# Accessories.net
KiCad netlist of a schematic drawn in Altium Designer
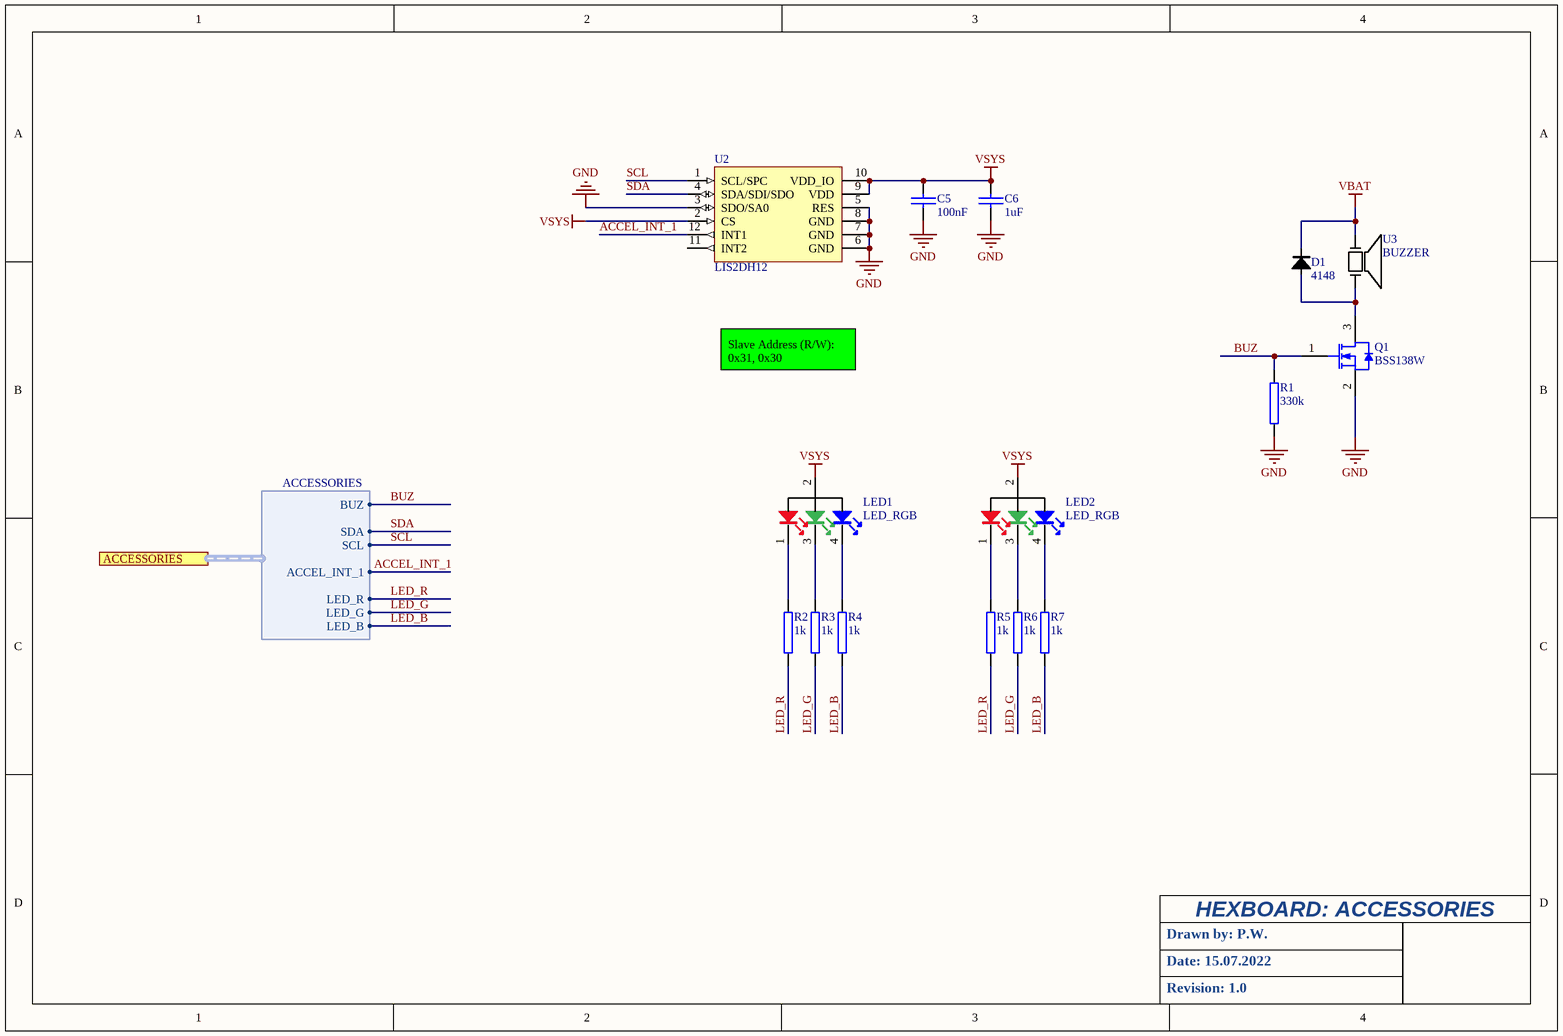
[diagram p0: Accessories.SchDoc]

(export (version "E")
  (design (tool "Eeschema 10.0.6"))
  (components
    (comp (ref "C5")
      (value "100nF")
      (footprint "C0603L")
      (description "Capacitor")
      (libsource (lib "LIB_PW") (part "CAP"))
    )
    (comp (ref "C6")
      (value "1uF")
      (footprint "C0603L")
      (description "Capacitor")
      (libsource (lib "LIB_PW") (part "CAP"))
    )
    (comp (ref "D1")
      (value "4148")
      (footprint "0603-DIODE")
      (description "DIODE")
      (libsource (lib "LIB_PW") (part "D"))
    )
    (comp (ref "LED1")
      (value "LED_RGB")
      (footprint "LED_604APFA3010LSEEZGKQ")
      (description "Red/green/blue LED")
      (libsource (lib "LIB_PW") (part "LED_RGB_2"))
    )
    (comp (ref "LED2")
      (value "LED_RGB")
      (footprint "LED_604APFA3010LSEEZGKQ")
      (description "Red/green/blue LED")
      (libsource (lib "LIB_PW") (part "LED_RGB_2"))
    )
    (comp (ref "Q1")
      (value "BSS138W")
      (footprint "SOT-323")
      (description "N-MOSFET")
      (libsource (lib "LIB_PW") (part "BSS138W"))
    )
    (comp (ref "R1") (value "330k") (footprint "1608[0603]") (libsource (lib "LIB_PW") (part "RES")))
    (comp (ref "R2") (value "1k") (footprint "1608[0603]") (libsource (lib "LIB_PW") (part "RES")))
    (comp (ref "R3") (value "1k") (footprint "1608[0603]") (libsource (lib "LIB_PW") (part "RES")))
    (comp (ref "R4") (value "1k") (footprint "1608[0603]") (libsource (lib "LIB_PW") (part "RES")))
    (comp (ref "R5") (value "1k") (footprint "1608[0603]") (libsource (lib "LIB_PW") (part "RES")))
    (comp (ref "R6") (value "1k") (footprint "1608[0603]") (libsource (lib "LIB_PW") (part "RES")))
    (comp (ref "R7") (value "1k") (footprint "1608[0603]") (libsource (lib "LIB_PW") (part "RES")))
    (comp (ref "U2")
      (value "LIS2DH12")
      (footprint "LGA50P200X200X100-12N")
      (description "3-axis - ±2g/±4g/±8g/±16g digital output femto accelerometer")
      (fields
        (field (name "MANUFACTURER") "STMicroelectronics")
        (field (name "2ND SOURCE PART NUMBER") "243-3081")
        (field (name "PUBLISHER") "Nordic Semiconductor")
      )
      (libsource (lib "LIB_PW") (part "LIS2xx12"))
    )
    (comp (ref "U3") (value "BUZZER") (footprint "SMT28") (libsource (lib "LIB_PW") (part "BUZZER")))
  )
  (nets
    (net (code "2") (name "/ACCEL_INT_1") (class "Default")
      (node (ref "U2") (pin "12") (pinfunction "INT1_12") (pintype "output"))
    )
    (net (code "3") (name "/BUZ") (class "Default")
      (node (ref "Q1") (pin "1") (pinfunction "G_1") (pintype "passive"))
      (node (ref "R1") (pin "2") (pinfunction "2_2") (pintype "passive"))
    )
    (net (code "4") (name "/LED_B") (class "Default")
      (node (ref "R4") (pin "1") (pinfunction "1_1") (pintype "passive"))
      (node (ref "R7") (pin "1") (pinfunction "1_1") (pintype "passive"))
    )
    (net (code "5") (name "/LED_G") (class "Default")
      (node (ref "R3") (pin "1") (pinfunction "1_1") (pintype "passive"))
      (node (ref "R6") (pin "1") (pinfunction "1_1") (pintype "passive"))
    )
    (net (code "6") (name "/LED_R") (class "Default")
      (node (ref "R2") (pin "1") (pinfunction "1_1") (pintype "passive"))
      (node (ref "R5") (pin "1") (pinfunction "1_1") (pintype "passive"))
    )
    (net (code "7") (name "/SCL") (class "Default")
      (node (ref "U2") (pin "1") (pinfunction "SCL/SPC_1") (pintype "input"))
    )
    (net (code "8") (name "/SDA") (class "Default")
      (node (ref "U2") (pin "4") (pinfunction "SDA/SDI/SDO_4") (pintype "bidirectional"))
    )
    (net (code "10") (name "GND") (class "Default")
      (node (ref "C5") (pin "2") (pinfunction "2_2") (pintype "passive"))
      (node (ref "C6") (pin "2") (pinfunction "2_2") (pintype "passive"))
      (node (ref "Q1") (pin "2") (pinfunction "S_2") (pintype "passive"))
      (node (ref "R1") (pin "1") (pinfunction "1_1") (pintype "passive"))
      (node (ref "U2") (pin "3") (pinfunction "SDO/SA0_3") (pintype "bidirectional"))
      (node (ref "U2") (pin "5") (pinfunction "RES_5") (pintype "passive"))
      (node (ref "U2") (pin "6") (pinfunction "GND_6") (pintype "power_in"))
      (node (ref "U2") (pin "7") (pinfunction "GND_7") (pintype "power_in"))
      (node (ref "U2") (pin "8") (pinfunction "GND_8") (pintype "power_in"))
    )
    (net (code "11") (name "Net-(D1-A)") (class "Default")
      (node (ref "D1") (pin "1") (pinfunction "A_1") (pintype "passive"))
      (node (ref "Q1") (pin "3") (pinfunction "D_3") (pintype "passive"))
      (node (ref "U3") (pin "1") (pinfunction "1_1") (pintype "passive"))
    )
    (net (code "12") (name "Net-(LED1-AB)") (class "Default")
      (node (ref "LED1") (pin "4") (pinfunction "AB_4") (pintype "passive"))
      (node (ref "R4") (pin "2") (pinfunction "2_2") (pintype "passive"))
    )
    (net (code "13") (name "Net-(LED1-KB)") (class "Default")
      (node (ref "LED1") (pin "3") (pinfunction "KB_3") (pintype "passive"))
      (node (ref "R3") (pin "2") (pinfunction "2_2") (pintype "passive"))
    )
    (net (code "14") (name "Net-(LED1-KR)") (class "Default")
      (node (ref "LED1") (pin "1") (pinfunction "KR_1") (pintype "passive"))
      (node (ref "R2") (pin "2") (pinfunction "2_2") (pintype "passive"))
    )
    (net (code "15") (name "Net-(LED2-AB)") (class "Default")
      (node (ref "LED2") (pin "4") (pinfunction "AB_4") (pintype "passive"))
      (node (ref "R7") (pin "2") (pinfunction "2_2") (pintype "passive"))
    )
    (net (code "16") (name "Net-(LED2-KB)") (class "Default")
      (node (ref "LED2") (pin "3") (pinfunction "KB_3") (pintype "passive"))
      (node (ref "R6") (pin "2") (pinfunction "2_2") (pintype "passive"))
    )
    (net (code "17") (name "Net-(LED2-KR)") (class "Default")
      (node (ref "LED2") (pin "1") (pinfunction "KR_1") (pintype "passive"))
      (node (ref "R5") (pin "2") (pinfunction "2_2") (pintype "passive"))
    )
    (net (code "18") (name "VBAT") (class "Default")
      (node (ref "D1") (pin "2") (pinfunction "K_2") (pintype "passive"))
      (node (ref "U3") (pin "2") (pinfunction "2_2") (pintype "passive"))
    )
    (net (code "19") (name "VSYS") (class "Default")
      (node (ref "C5") (pin "1") (pinfunction "1_1") (pintype "passive"))
      (node (ref "C6") (pin "1") (pinfunction "1_1") (pintype "passive"))
      (node (ref "LED1") (pin "2") (pinfunction "KG_2") (pintype "passive"))
      (node (ref "LED2") (pin "2") (pinfunction "KG_2") (pintype "passive"))
      (node (ref "U2") (pin "10") (pinfunction "VDD_IO_10") (pintype "power_in"))
      (node (ref "U2") (pin "2") (pinfunction "CS_2") (pintype "input"))
      (node (ref "U2") (pin "9") (pinfunction "VDD_9") (pintype "power_in"))
    )
    (net (code "20") (name "unconnected-(U2-INT2-Pad11)") (class "Default")
      (node (ref "U2") (pin "11") (pinfunction "INT2_11") (pintype "output"))
    )
  )
)
